# Schema_elettronico_Bluetooth_Switch.net
KiCad netlist of a schematic drawn in EasyEDA
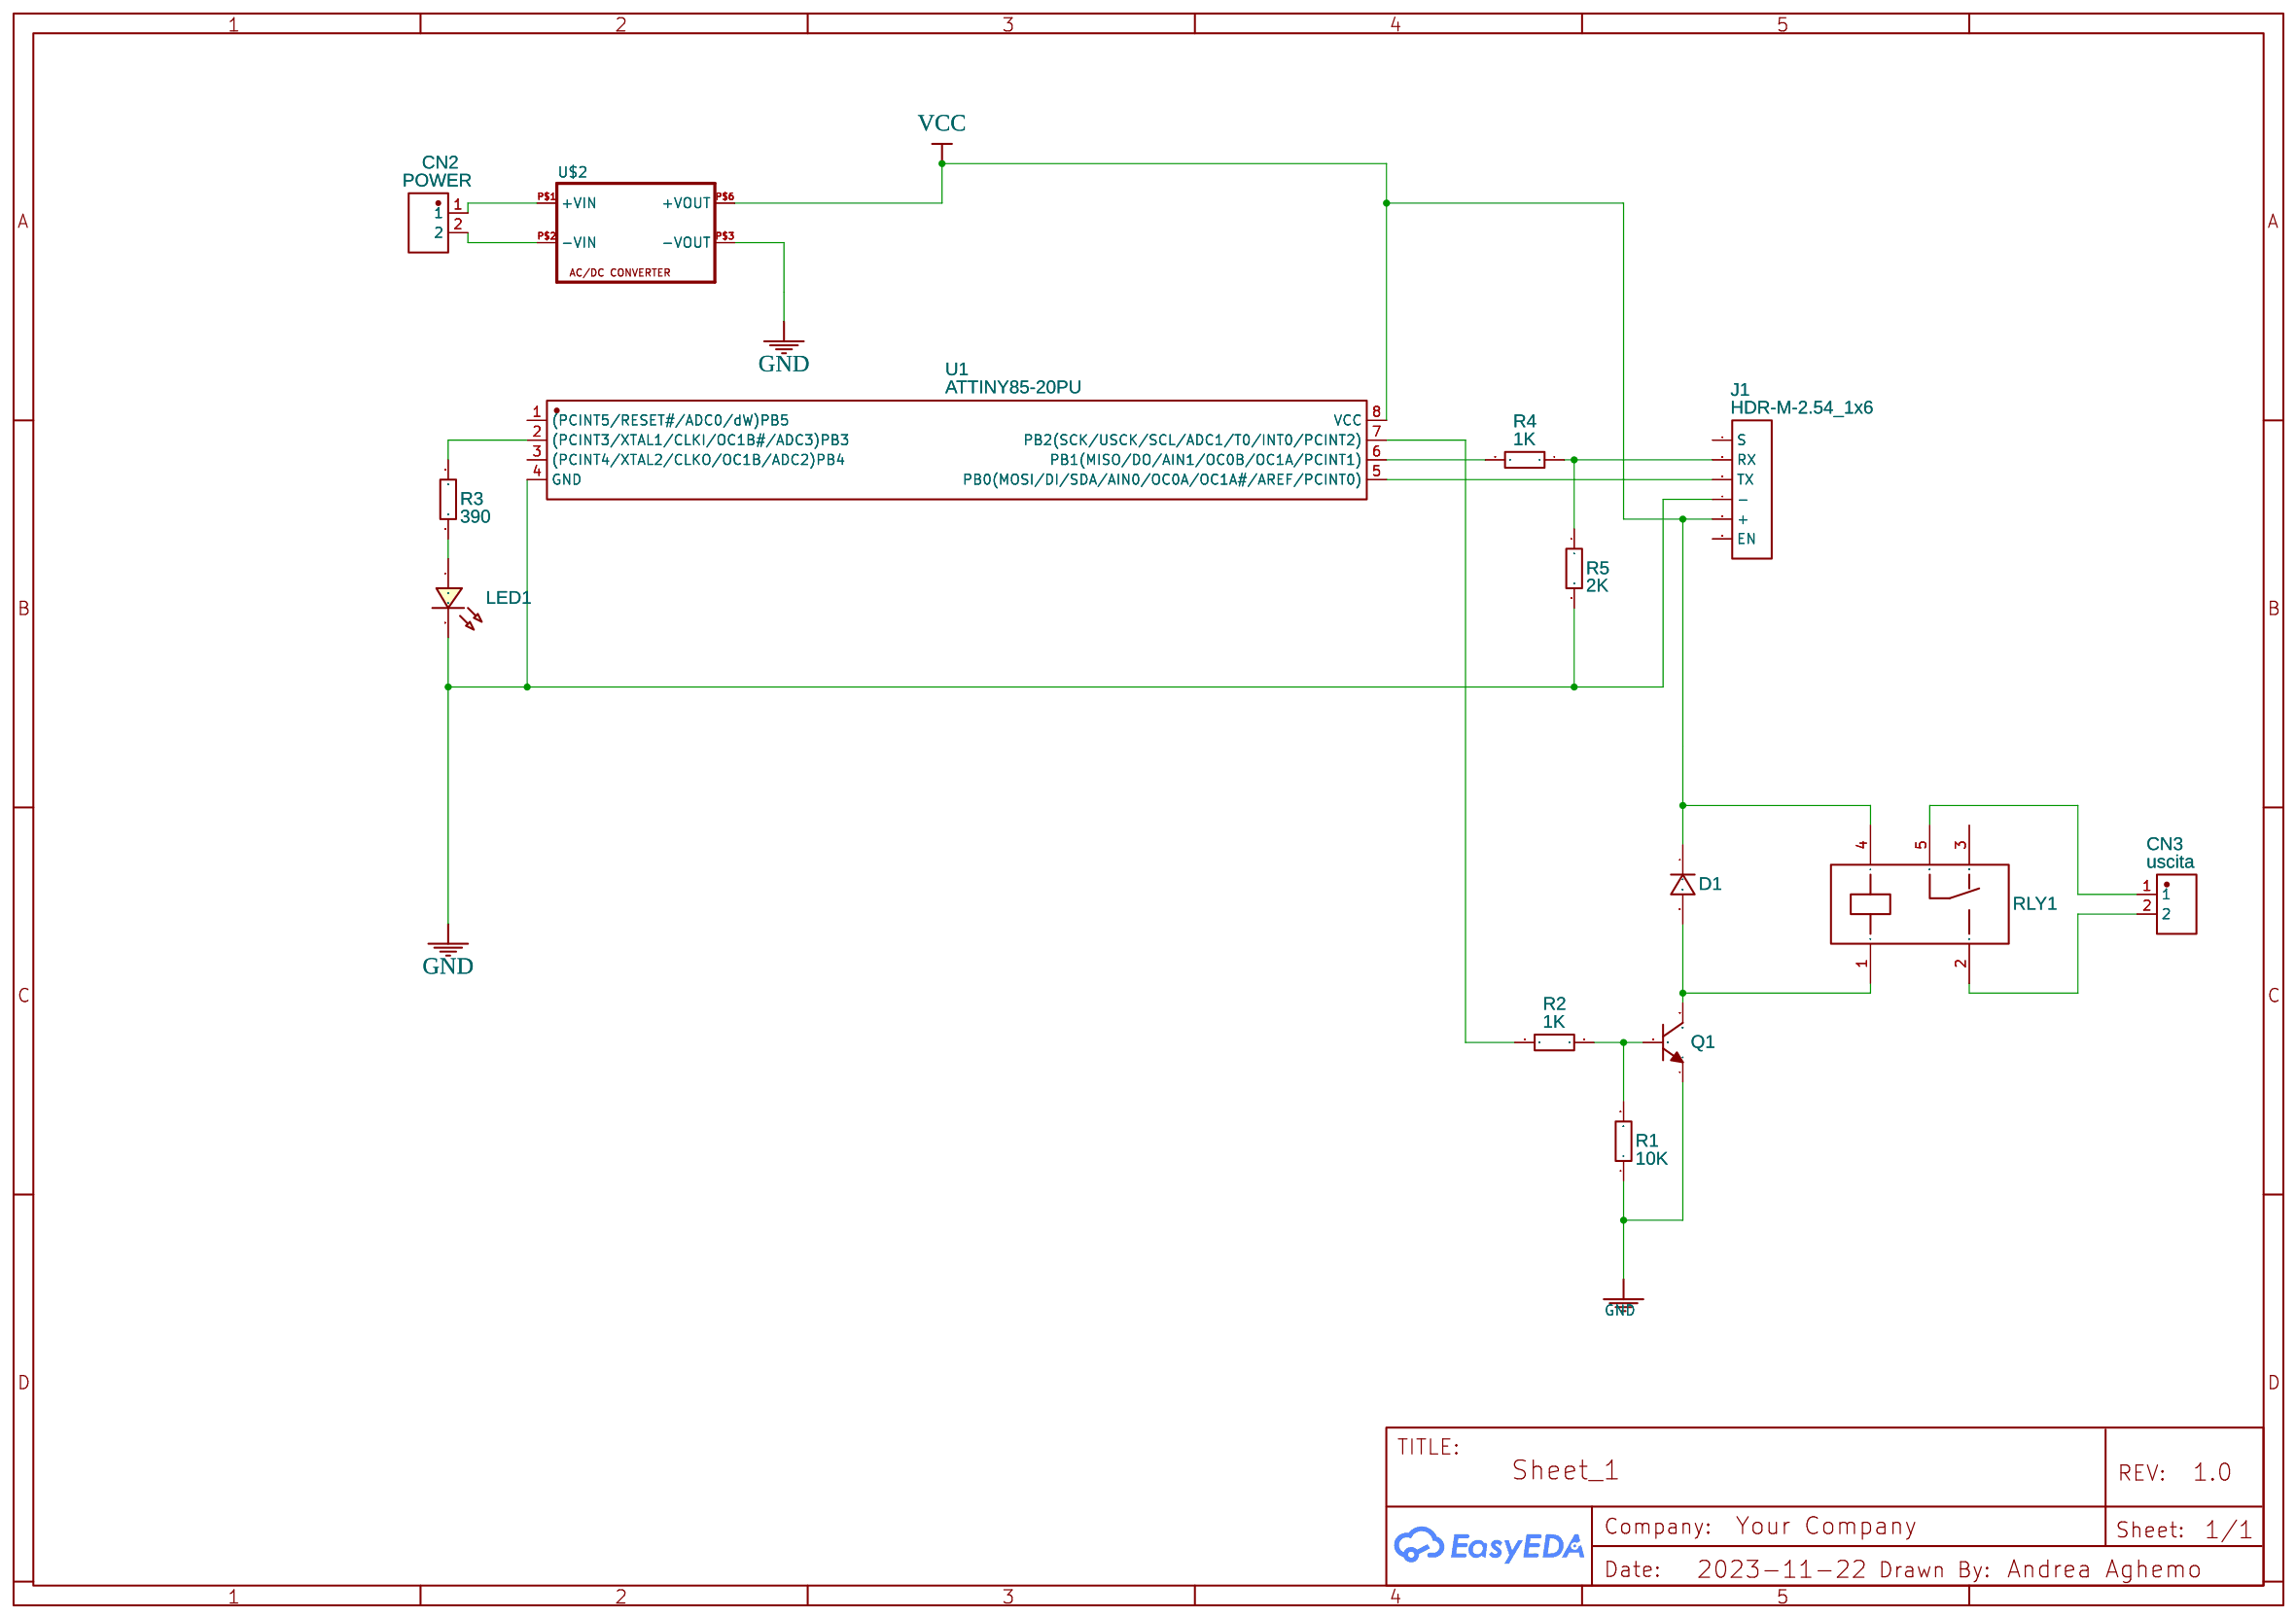
[diagram p0: schematic sheet]

(export (version "E")
  (design (tool "Eeschema 10.0.6"))
  (components
    (comp (ref "CN2")
      (value "POWER")
      (fields
        (field (name "Manufacturer Part") "MX126-5.0-GN01-02P-Cu-S-A")
        (field (name "Manufacturer") "MAX(迈旭)")
      )
      (libsource (lib "") (part "MX126-5.0-GN01-02P-CU-S-A_1"))
    )
    (comp (ref "CN3")
      (value "uscita")
      (fields
        (field (name "Manufacturer Part") "MX126-5.0-GN01-02P-Cu-S-A")
        (field (name "Manufacturer") "MAX(迈旭)")
      )
      (libsource (lib "") (part "MX126-5.0-GN01-02P-CU-S-A"))
    )
    (comp (ref "D1")
      (value "1N4007")
      (fields (field (name "Manufacturer Part") "1N4007-SOD123"))
      (libsource (lib "") (part "1N4007-SOD123"))
    )
    (comp (ref "J1") (value "HDR-M-2.54_1x6") (libsource (lib "") (part "HDR-M-2.54_1x6")))
    (comp (ref "LED1")
      (value "LED-0805_B")
      (fields (field (name "Manufacturer Part") "D-B080508B1-KS2") (field (name "Manufacturer") "方舟 ARKLED"))
      (libsource (lib "") (part "LED-0805_B"))
    )
    (comp (ref "Q1")
      (value "2N3904")
      (fields (field (name "Manufacturer Part") "2n3904S-RTK/PS") (field (name "Manufacturer") "KEC"))
      (libsource (lib "") (part "2N3904(SOT-23)"))
    )
    (comp (ref "R1")
      (value "10K")
      (fields (field (name "Manufacturer Part") "RK73B1JTTD103J") (field (name "Manufacturer") "KOA"))
      (libsource (lib "") (part "RK73B1JTTD103J_1"))
    )
    (comp (ref "R2")
      (value "1K")
      (fields (field (name "Manufacturer Part") "RK73B1JTTD103J") (field (name "Manufacturer") "KOA"))
      (libsource (lib "") (part "RK73B1JTTD103J_2"))
    )
    (comp (ref "R3")
      (value "390")
      (fields (field (name "Manufacturer Part") "RK73B1JTTD103J") (field (name "Manufacturer") "KOA"))
      (libsource (lib "") (part "RK73B1JTTD103J_1"))
    )
    (comp (ref "R4")
      (value "1K")
      (fields (field (name "Manufacturer Part") "RK73B1JTTD103J") (field (name "Manufacturer") "KOA"))
      (libsource (lib "") (part "RK73B1JTTD103J_2"))
    )
    (comp (ref "R5")
      (value "2K")
      (fields (field (name "Manufacturer Part") "RK73B1JTTD103J") (field (name "Manufacturer") "KOA"))
      (libsource (lib "") (part "RK73B1JTTD103J"))
    )
    (comp (ref "RLY1")
      (value "SRD-05VDC-SL-C")
      (fields (field (name "Manufacturer") "松乐"))
      (libsource (lib "") (part "SRD-05VDC-SL-C"))
    )
    (comp (ref "U$2") (value "AC-DC-CONVERTER_SUCA11") (libsource (lib "") (part "Unknown_315_-700")))
    (comp (ref "U1")
      (value "ATTINY85-20PU")
      (fields (field (name "Manufacturer") "MICROCHIP(美国微芯)"))
      (libsource (lib "") (part "ATTINY85-20PU"))
    )
  )
  (nets
    (net (code "1") (name "GND") (class "Default")
      (node (ref "J1") (pin "4") (pinfunction "-_4") (pintype "input"))
      (node (ref "LED1") (pin "2") (pinfunction "2_2") (pintype "unspecified"))
      (node (ref "Q1") (pin "1") (pinfunction "E_1") (pintype "input"))
      (node (ref "R1") (pin "1") (pinfunction "1_1") (pintype "unspecified"))
      (node (ref "R5") (pin "2") (pinfunction "2_2") (pintype "unspecified"))
      (node (ref "U$2") (pin "P$3") (pinfunction "-VOUT_P$3") (pintype "bidirectional"))
      (node (ref "U1") (pin "4") (pinfunction "GND_4") (pintype "unspecified"))
    )
    (net (code "2") (name "Net-(CN3-Pad1)") (class "Default")
      (node (ref "CN3") (pin "1") (pinfunction "1_1") (pintype "unspecified"))
      (node (ref "RLY1") (pin "5") (pinfunction "5_5") (pintype "input"))
    )
    (net (code "3") (name "Net-(CN3-Pad2)") (class "Default")
      (node (ref "CN3") (pin "2") (pinfunction "2_2") (pintype "unspecified"))
      (node (ref "RLY1") (pin "2") (pinfunction "2_2") (pintype "input"))
    )
    (net (code "4") (name "Net-(J1-RX)") (class "Default")
      (node (ref "J1") (pin "2") (pinfunction "RX_2") (pintype "input"))
      (node (ref "R4") (pin "1") (pinfunction "1_1") (pintype "unspecified"))
      (node (ref "R5") (pin "1") (pinfunction "1_1") (pintype "unspecified"))
    )
    (net (code "5") (name "Net-(J1-TX)") (class "Default")
      (node (ref "J1") (pin "3") (pinfunction "TX_3") (pintype "input"))
      (node (ref "U1") (pin "5") (pinfunction "PB0(MOSI/DI/SDA/AIN0/OC0A/OC1A#/AREF/PCINT0)_5") (pintype "unspecified"))
    )
    (net (code "6") (name "Net-(LED1-Pad1)") (class "Default")
      (node (ref "LED1") (pin "1") (pinfunction "1_1") (pintype "unspecified"))
      (node (ref "R3") (pin "1") (pinfunction "1_1") (pintype "unspecified"))
    )
    (net (code "7") (name "Net-(Q1-B)") (class "Default")
      (node (ref "Q1") (pin "2") (pinfunction "B_2") (pintype "input"))
      (node (ref "R1") (pin "2") (pinfunction "2_2") (pintype "unspecified"))
      (node (ref "R2") (pin "1") (pinfunction "1_1") (pintype "unspecified"))
    )
    (net (code "8") (name "Net-(Q1-C)") (class "Default")
      (node (ref "D1") (pin "2") (pinfunction "2_2") (pintype "unspecified"))
      (node (ref "Q1") (pin "3") (pinfunction "C_3") (pintype "input"))
      (node (ref "RLY1") (pin "1") (pinfunction "1_1") (pintype "input"))
    )
    (net (code "9") (name "Net-(U$2-+VIN)") (class "Default")
      (node (ref "CN2") (pin "1") (pinfunction "1_1") (pintype "unspecified"))
      (node (ref "U$2") (pin "P$1") (pinfunction "+VIN_P$1") (pintype "bidirectional"))
    )
    (net (code "10") (name "Net-(U$2--VIN)") (class "Default")
      (node (ref "CN2") (pin "2") (pinfunction "2_2") (pintype "unspecified"))
      (node (ref "U$2") (pin "P$2") (pinfunction "-VIN_P$2") (pintype "bidirectional"))
    )
    (net (code "11") (name "Net-(U1-(PCINT3{slash}XTAL1{slash}CLKI{slash}OC1B#{slash}ADC3)PB3)") (class "Default")
      (node (ref "R3") (pin "2") (pinfunction "2_2") (pintype "unspecified"))
      (node (ref "U1") (pin "2") (pinfunction "(PCINT3/XTAL1/CLKI/OC1B#/ADC3)PB3_2") (pintype "unspecified"))
    )
    (net (code "12") (name "Net-(U1-PB1(MISO{slash}DO{slash}AIN1{slash}OC0B{slash}OC1A{slash}PCINT1))") (class "Default")
      (node (ref "R4") (pin "2") (pinfunction "2_2") (pintype "unspecified"))
      (node (ref "U1") (pin "6") (pinfunction "PB1(MISO/DO/AIN1/OC0B/OC1A/PCINT1)_6") (pintype "unspecified"))
    )
    (net (code "13") (name "Net-(U1-PB2(SCK{slash}USCK{slash}SCL{slash}ADC1{slash}T0{slash}INT0{slash}PCINT2))") (class "Default")
      (node (ref "R2") (pin "2") (pinfunction "2_2") (pintype "unspecified"))
      (node (ref "U1") (pin "7") (pinfunction "PB2(SCK/USCK/SCL/ADC1/T0/INT0/PCINT2)_7") (pintype "unspecified"))
    )
    (net (code "14") (name "VCC") (class "Default")
      (node (ref "D1") (pin "1") (pinfunction "1_1") (pintype "unspecified"))
      (node (ref "J1") (pin "5") (pinfunction "+_5") (pintype "input"))
      (node (ref "RLY1") (pin "4") (pinfunction "4_4") (pintype "input"))
      (node (ref "U$2") (pin "P$6") (pinfunction "+VOUT_P$6") (pintype "bidirectional"))
      (node (ref "U1") (pin "8") (pinfunction "VCC_8") (pintype "unspecified"))
    )
    (net (code "15") (name "unconnected-(J1-EN-Pad6)") (class "Default")
      (node (ref "J1") (pin "6") (pinfunction "EN_6") (pintype "input"))
    )
    (net (code "16") (name "unconnected-(J1-S-Pad1)") (class "Default")
      (node (ref "J1") (pin "1") (pinfunction "S_1") (pintype "input"))
    )
    (net (code "17") (name "unconnected-(RLY1-Pad3)") (class "Default")
      (node (ref "RLY1") (pin "3") (pinfunction "3_3") (pintype "input"))
    )
    (net (code "18") (name "unconnected-(U1-(PCINT4{slash}XTAL2{slash}CLKO{slash}OC1B{slash}ADC2)PB4-Pad3)") (class "Default")
      (node (ref "U1") (pin "3") (pinfunction "(PCINT4/XTAL2/CLKO/OC1B/ADC2)PB4_3") (pintype "unspecified"))
    )
    (net (code "19") (name "unconnected-(U1-(PCINT5{slash}RESET#{slash}ADC0{slash}dW)PB5-Pad1)") (class "Default")
      (node (ref "U1") (pin "1") (pinfunction "(PCINT5/RESET#/ADC0/dW)PB5_1") (pintype "unspecified"))
    )
  )
)
